# alim.net
KiCad netlist of a schematic drawn in Altium Designer
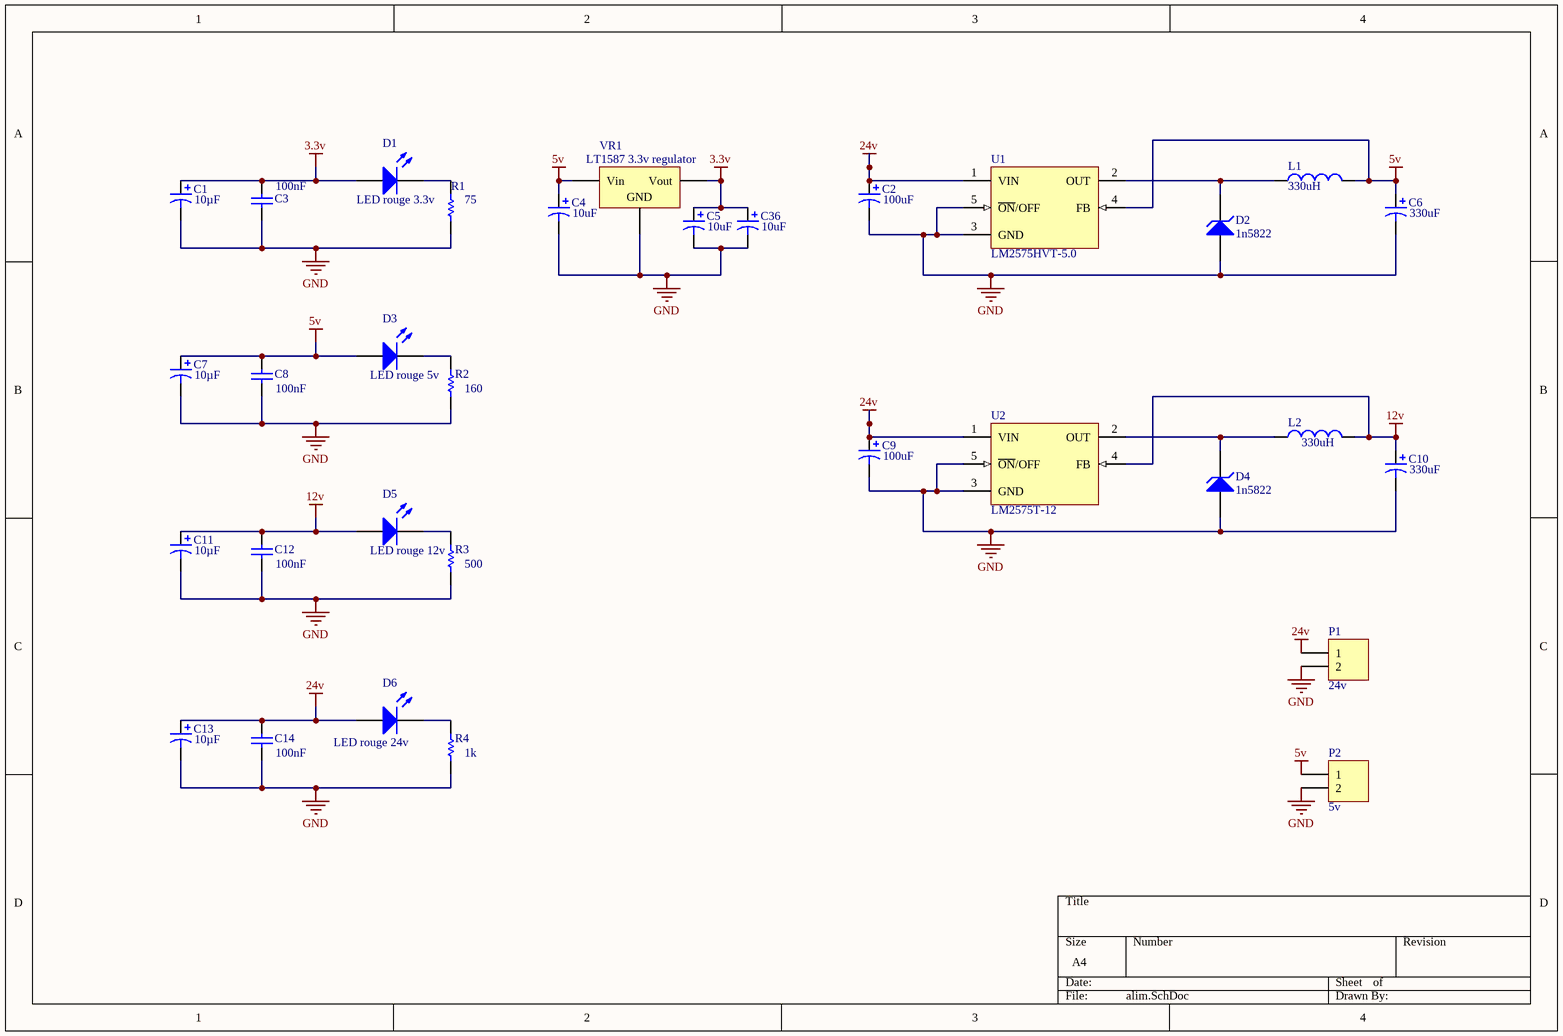
[diagram p0: alim.SchDoc]

(export (version "E")
  (design (tool "Eeschema 10.0.6"))
  (components
    (comp (ref "C1")
      (value "10µF")
      (footprint "CAPC3216L")
      (description "Polarized Capacitor (Surface Mount)")
      (fields (field (name "Comment") "Cap Pol3") (field (name "PUBLISHER") "Altium Limited"))
      (libsource (lib "Miscellaneous Devices") (part "Cap Pol3"))
    )
    (comp (ref "C2")
      (value "100uF")
      (footprint "CAPPR2-5x6.8")
      (description "Polarized Capacitor (Surface Mount)")
      (fields (field (name "Comment") "Cap Pol3") (field (name "PUBLISHER") "Altium Limited"))
      (libsource (lib "Miscellaneous Devices") (part "Cap Pol3"))
    )
    (comp (ref "C3")
      (value "100nF")
      (footprint "CAPC1608L")
      (description "Capacitor")
      (fields (field (name "Comment") "Cap") (field (name "PUBLISHER") "Altium Limited"))
      (libsource (lib "Miscellaneous Devices") (part "Cap"))
    )
    (comp (ref "C4")
      (value "10uF")
      (footprint "CAPC3216L")
      (description "Polarized Capacitor (Surface Mount)")
      (fields (field (name "Comment") "Cap Pol3") (field (name "PUBLISHER") "Altium Limited"))
      (libsource (lib "Miscellaneous Devices") (part "Cap Pol3"))
    )
    (comp (ref "C5")
      (value "10uF")
      (footprint "CAPC3216L")
      (description "Polarized Capacitor (Surface Mount)")
      (fields (field (name "Comment") "Cap Pol3") (field (name "PUBLISHER") "Altium Limited"))
      (libsource (lib "Miscellaneous Devices") (part "Cap Pol3"))
    )
    (comp (ref "C6")
      (value "330uF")
      (footprint "CAPPR5-10x12.5")
      (description "Polarized Capacitor (Surface Mount)")
      (fields (field (name "Comment") "Cap Pol3") (field (name "PUBLISHER") "Altium Limited"))
      (libsource (lib "Miscellaneous Devices") (part "Cap Pol3"))
    )
    (comp (ref "C7")
      (value "10µF")
      (footprint "CAPC3216L")
      (description "Polarized Capacitor (Surface Mount)")
      (fields (field (name "Comment") "Cap Pol3") (field (name "PUBLISHER") "Altium Limited"))
      (libsource (lib "Miscellaneous Devices") (part "Cap Pol3"))
    )
    (comp (ref "C8")
      (value "100nF")
      (footprint "CAPC1608L")
      (description "Capacitor")
      (fields (field (name "Comment") "Cap") (field (name "PUBLISHER") "Altium Limited"))
      (libsource (lib "Miscellaneous Devices") (part "Cap"))
    )
    (comp (ref "C9")
      (value "100uF")
      (footprint "CAPPR2-5x6.8")
      (description "Polarized Capacitor (Surface Mount)")
      (fields (field (name "Comment") "Cap Pol3") (field (name "PUBLISHER") "Altium Limited"))
      (libsource (lib "Miscellaneous Devices") (part "Cap Pol3"))
    )
    (comp (ref "C10")
      (value "330uF")
      (footprint "CAPPR5-10x12.5")
      (description "Polarized Capacitor (Surface Mount)")
      (fields (field (name "Comment") "Cap Pol3") (field (name "PUBLISHER") "Altium Limited"))
      (libsource (lib "Miscellaneous Devices") (part "Cap Pol3"))
    )
    (comp (ref "C11")
      (value "10µF")
      (footprint "CAPC3216L")
      (description "Polarized Capacitor (Surface Mount)")
      (fields (field (name "Comment") "Cap Pol3") (field (name "PUBLISHER") "Altium Limited"))
      (libsource (lib "Miscellaneous Devices") (part "Cap Pol3"))
    )
    (comp (ref "C12")
      (value "100nF")
      (footprint "CAPC1608L")
      (description "Capacitor")
      (fields (field (name "Comment") "Cap") (field (name "PUBLISHER") "Altium Limited"))
      (libsource (lib "Miscellaneous Devices") (part "Cap"))
    )
    (comp (ref "C13")
      (value "10µF")
      (footprint "CAPC3216L")
      (description "Polarized Capacitor (Surface Mount)")
      (fields (field (name "Comment") "Cap Pol3") (field (name "PUBLISHER") "Altium Limited"))
      (libsource (lib "Miscellaneous Devices") (part "Cap Pol3"))
    )
    (comp (ref "C14")
      (value "100nF")
      (footprint "CAPC1608L")
      (description "Capacitor")
      (fields (field (name "Comment") "Cap") (field (name "PUBLISHER") "Altium Limited"))
      (libsource (lib "Miscellaneous Devices") (part "Cap"))
    )
    (comp (ref "C36")
      (value "10uF")
      (footprint "CAPC3216L")
      (description "Polarized Capacitor (Surface Mount)")
      (fields (field (name "Comment") "Cap Pol3") (field (name "PUBLISHER") "Altium Limited"))
      (libsource (lib "Miscellaneous Devices") (part "Cap Pol3"))
    )
    (comp (ref "D1")
      (value "LED rouge 3.3v")
      (footprint "3.2X1.6X1.1")
      (description "Typical RED, GREEN, YELLOW, AMBER GaAs LED")
      (fields (field (name "PUBLISHER") "Altium Limited"))
      (libsource (lib "Miscellaneous Devices") (part "LED2"))
    )
    (comp (ref "D2")
      (value "1n5822")
      (footprint "DIO18.84-9.6x5.6")
      (description "Zener Diode")
      (fields (field (name "PUBLISHER") "Altium Limited"))
      (libsource (lib "Miscellaneous Devices") (part "D Zener"))
    )
    (comp (ref "D3")
      (value "LED rouge 5v")
      (footprint "3.2X1.6X1.1")
      (description "Typical RED, GREEN, YELLOW, AMBER GaAs LED")
      (fields (field (name "PUBLISHER") "Altium Limited"))
      (libsource (lib "Miscellaneous Devices") (part "LED2"))
    )
    (comp (ref "D4")
      (value "1n5822")
      (footprint "DIODE-0.7")
      (description "Zener Diode")
      (fields (field (name "PUBLISHER") "Altium Limited"))
      (libsource (lib "Miscellaneous Devices") (part "D Zener"))
    )
    (comp (ref "D5")
      (value "LED rouge 12v")
      (footprint "3.2X1.6X1.1")
      (description "Typical RED, GREEN, YELLOW, AMBER GaAs LED")
      (fields (field (name "PUBLISHER") "Altium Limited"))
      (libsource (lib "Miscellaneous Devices") (part "LED2"))
    )
    (comp (ref "D6")
      (value "LED rouge 24v")
      (footprint "3.2X1.6X1.1")
      (description "Typical RED, GREEN, YELLOW, AMBER GaAs LED")
      (fields (field (name "PUBLISHER") "Altium Limited"))
      (libsource (lib "Miscellaneous Devices") (part "LED2"))
    )
    (comp (ref "L1")
      (value "330uH")
      (footprint "CAPC4532L")
      (description "Inductor")
      (fields (field (name "PUBLISHER") "Altium Limited"))
      (libsource (lib "Miscellaneous Devices") (part "Inductor"))
    )
    (comp (ref "L2")
      (value "330uH")
      (footprint "CAPC4532L")
      (description "Inductor")
      (fields (field (name "PUBLISHER") "Altium Limited"))
      (libsource (lib "Miscellaneous Devices") (part "Inductor"))
    )
    (comp (ref "P1")
      (value "24v")
      (footprint "power connector")
      (description "Header, 2-Pin")
      (fields (field (name "PUBLISHER") "Altium Limited"))
      (libsource (lib "Miscellaneous Connectors") (part "Header 2"))
    )
    (comp (ref "P2")
      (value "5v")
      (footprint "power connector")
      (description "Header, 2-Pin")
      (fields (field (name "PUBLISHER") "Altium Limited"))
      (libsource (lib "Miscellaneous Connectors") (part "Header 2"))
    )
    (comp (ref "R1")
      (value "75")
      (footprint "RESC1608L")
      (description "Resistor")
      (fields (field (name "Comment") "Res1") (field (name "PUBLISHER") "Altium Limited"))
      (libsource (lib "Miscellaneous Devices") (part "Res1"))
    )
    (comp (ref "R2")
      (value "160")
      (footprint "RESC1608L")
      (description "Resistor")
      (fields (field (name "Comment") "Res1") (field (name "PUBLISHER") "Altium Limited"))
      (libsource (lib "Miscellaneous Devices") (part "Res1"))
    )
    (comp (ref "R3")
      (value "500")
      (footprint "RESC1608L")
      (description "Resistor")
      (fields (field (name "Comment") "Res1") (field (name "PUBLISHER") "Altium Limited"))
      (libsource (lib "Miscellaneous Devices") (part "Res1"))
    )
    (comp (ref "R4")
      (value "1k")
      (footprint "RESC1608L")
      (description "Resistor")
      (fields (field (name "Comment") "Res1") (field (name "PUBLISHER") "Altium Limited"))
      (libsource (lib "Miscellaneous Devices") (part "Res1"))
    )
    (comp (ref "U1")
      (value "LM2575HVT-5.0")
      (footprint "TO170P1524X460-6N")
      (description "SIMPLE SWITCHER 1A Step-Down Voltage Regulator")
      (fields
        (field (name "MANUFACTURER") "National Semiconductor")
        (field (name "DIGIKEYPARTNUMBER") "LM2575HVT-5.0-ND")
        (field (name "PUBLISHER") "Altium Limited")
      )
      (libsource (lib "NSC Switcher") (part "LM2575HVT-5.0"))
    )
    (comp (ref "U2")
      (value "LM2575T-12")
      (footprint "TO170P1524X460-6N")
      (description "SIMPLE SWITCHER 1A Step-Down Voltage Regulator")
      (fields
        (field (name "MANUFACTURER") "National Semiconductor")
        (field (name "DIGIKEYPARTNUMBER") "LM2575T-12-ND")
        (field (name "PUBLISHER") "Altium Limited")
      )
      (libsource (lib "NSC Switcher") (part "LM2575T-12"))
    )
    (comp (ref "VR1")
      (value "LT1587 3.3v regulator")
      (footprint "TO254P1435X457-4N")
      (description "Voltage Regulator")
      (fields (field (name "PUBLISHER") "Altium Limited"))
      (libsource (lib "Miscellaneous Devices") (part "Volt Reg"))
    )
  )
  (nets
    (net (code "1") (name "3.3v") (class "Default")
      (node (ref "C1") (pin "1") (pinfunction "1_1") (pintype "passive"))
      (node (ref "C3") (pin "2") (pinfunction "2_2") (pintype "passive"))
      (node (ref "C36") (pin "1") (pinfunction "1_1") (pintype "passive"))
      (node (ref "C5") (pin "1") (pinfunction "1_1") (pintype "passive"))
      (node (ref "D1") (pin "1") (pinfunction "A_1") (pintype "passive"))
      (node (ref "VR1") (pin "3") (pinfunction "Vout_3") (pintype "passive"))
    )
    (net (code "2") (name "5v") (class "Default")
      (node (ref "C4") (pin "1") (pinfunction "1_1") (pintype "passive"))
      (node (ref "C6") (pin "1") (pinfunction "1_1") (pintype "passive"))
      (node (ref "C7") (pin "1") (pinfunction "1_1") (pintype "passive"))
      (node (ref "C8") (pin "2") (pinfunction "2_2") (pintype "passive"))
      (node (ref "D3") (pin "1") (pinfunction "A_1") (pintype "passive"))
      (node (ref "L1") (pin "2") (pinfunction "2_2") (pintype "passive"))
      (node (ref "P2") (pin "1") (pinfunction "1_1") (pintype "passive"))
      (node (ref "U1") (pin "4") (pinfunction "FB_4") (pintype "input"))
      (node (ref "VR1") (pin "1") (pinfunction "Vin_1") (pintype "passive"))
    )
    (net (code "3") (name "12v") (class "Default")
      (node (ref "C10") (pin "1") (pinfunction "1_1") (pintype "passive"))
      (node (ref "C11") (pin "1") (pinfunction "1_1") (pintype "passive"))
      (node (ref "C12") (pin "2") (pinfunction "2_2") (pintype "passive"))
      (node (ref "D5") (pin "1") (pinfunction "A_1") (pintype "passive"))
      (node (ref "L2") (pin "2") (pinfunction "2_2") (pintype "passive"))
      (node (ref "U2") (pin "4") (pinfunction "FB_4") (pintype "input"))
    )
    (net (code "4") (name "24v") (class "Default")
      (node (ref "C13") (pin "1") (pinfunction "1_1") (pintype "passive"))
      (node (ref "C14") (pin "2") (pinfunction "2_2") (pintype "passive"))
      (node (ref "C2") (pin "1") (pinfunction "1_1") (pintype "passive"))
      (node (ref "C9") (pin "1") (pinfunction "1_1") (pintype "passive"))
      (node (ref "D6") (pin "1") (pinfunction "A_1") (pintype "passive"))
      (node (ref "P1") (pin "1") (pinfunction "1_1") (pintype "passive"))
      (node (ref "U1") (pin "1") (pinfunction "VIN_1") (pintype "power_in"))
      (node (ref "U2") (pin "1") (pinfunction "VIN_1") (pintype "power_in"))
    )
    (net (code "5") (name "GND") (class "Default")
      (node (ref "C1") (pin "2") (pinfunction "2_2") (pintype "passive"))
      (node (ref "C10") (pin "2") (pinfunction "2_2") (pintype "passive"))
      (node (ref "C11") (pin "2") (pinfunction "2_2") (pintype "passive"))
      (node (ref "C12") (pin "1") (pinfunction "1_1") (pintype "passive"))
      (node (ref "C13") (pin "2") (pinfunction "2_2") (pintype "passive"))
      (node (ref "C14") (pin "1") (pinfunction "1_1") (pintype "passive"))
      (node (ref "C2") (pin "2") (pinfunction "2_2") (pintype "passive"))
      (node (ref "C3") (pin "1") (pinfunction "1_1") (pintype "passive"))
      (node (ref "C36") (pin "2") (pinfunction "2_2") (pintype "passive"))
      (node (ref "C4") (pin "2") (pinfunction "2_2") (pintype "passive"))
      (node (ref "C5") (pin "2") (pinfunction "2_2") (pintype "passive"))
      (node (ref "C6") (pin "2") (pinfunction "2_2") (pintype "passive"))
      (node (ref "C7") (pin "2") (pinfunction "2_2") (pintype "passive"))
      (node (ref "C8") (pin "1") (pinfunction "1_1") (pintype "passive"))
      (node (ref "C9") (pin "2") (pinfunction "2_2") (pintype "passive"))
      (node (ref "D2") (pin "1") (pinfunction "A_1") (pintype "passive"))
      (node (ref "D4") (pin "1") (pinfunction "A_1") (pintype "passive"))
      (node (ref "P1") (pin "2") (pinfunction "2_2") (pintype "passive"))
      (node (ref "P2") (pin "2") (pinfunction "2_2") (pintype "passive"))
      (node (ref "R1") (pin "1") (pinfunction "1_1") (pintype "passive"))
      (node (ref "R2") (pin "1") (pinfunction "1_1") (pintype "passive"))
      (node (ref "R3") (pin "1") (pinfunction "1_1") (pintype "passive"))
      (node (ref "R4") (pin "1") (pinfunction "1_1") (pintype "passive"))
      (node (ref "U1") (pin "3") (pinfunction "GND_3") (pintype "power_in"))
      (node (ref "U1") (pin "5") (pinfunction "~{ON}/OFF_5") (pintype "input"))
      (node (ref "U2") (pin "3") (pinfunction "GND_3") (pintype "power_in"))
      (node (ref "U2") (pin "5") (pinfunction "~{ON}/OFF_5") (pintype "input"))
      (node (ref "VR1") (pin "2") (pinfunction "GND_2") (pintype "passive"))
    )
    (net (code "6") (name "Net-(D1-K)") (class "Default")
      (node (ref "D1") (pin "2") (pinfunction "K_2") (pintype "passive"))
      (node (ref "R1") (pin "2") (pinfunction "2_2") (pintype "passive"))
    )
    (net (code "7") (name "Net-(D2-K)") (class "Default")
      (node (ref "D2") (pin "2") (pinfunction "K_2") (pintype "passive"))
      (node (ref "L1") (pin "1") (pinfunction "1_1") (pintype "passive"))
      (node (ref "U1") (pin "2") (pinfunction "OUT_2") (pintype "power_in"))
    )
    (net (code "8") (name "Net-(D3-K)") (class "Default")
      (node (ref "D3") (pin "2") (pinfunction "K_2") (pintype "passive"))
      (node (ref "R2") (pin "2") (pinfunction "2_2") (pintype "passive"))
    )
    (net (code "9") (name "Net-(D4-K)") (class "Default")
      (node (ref "D4") (pin "2") (pinfunction "K_2") (pintype "passive"))
      (node (ref "L2") (pin "1") (pinfunction "1_1") (pintype "passive"))
      (node (ref "U2") (pin "2") (pinfunction "OUT_2") (pintype "power_in"))
    )
    (net (code "10") (name "Net-(D5-K)") (class "Default")
      (node (ref "D5") (pin "2") (pinfunction "K_2") (pintype "passive"))
      (node (ref "R3") (pin "2") (pinfunction "2_2") (pintype "passive"))
    )
    (net (code "11") (name "Net-(D6-K)") (class "Default")
      (node (ref "D6") (pin "2") (pinfunction "K_2") (pintype "passive"))
      (node (ref "R4") (pin "2") (pinfunction "2_2") (pintype "passive"))
    )
  )
)
